# Drone_Mercury.net
KiCad netlist of a schematic drawn in Altium Designer
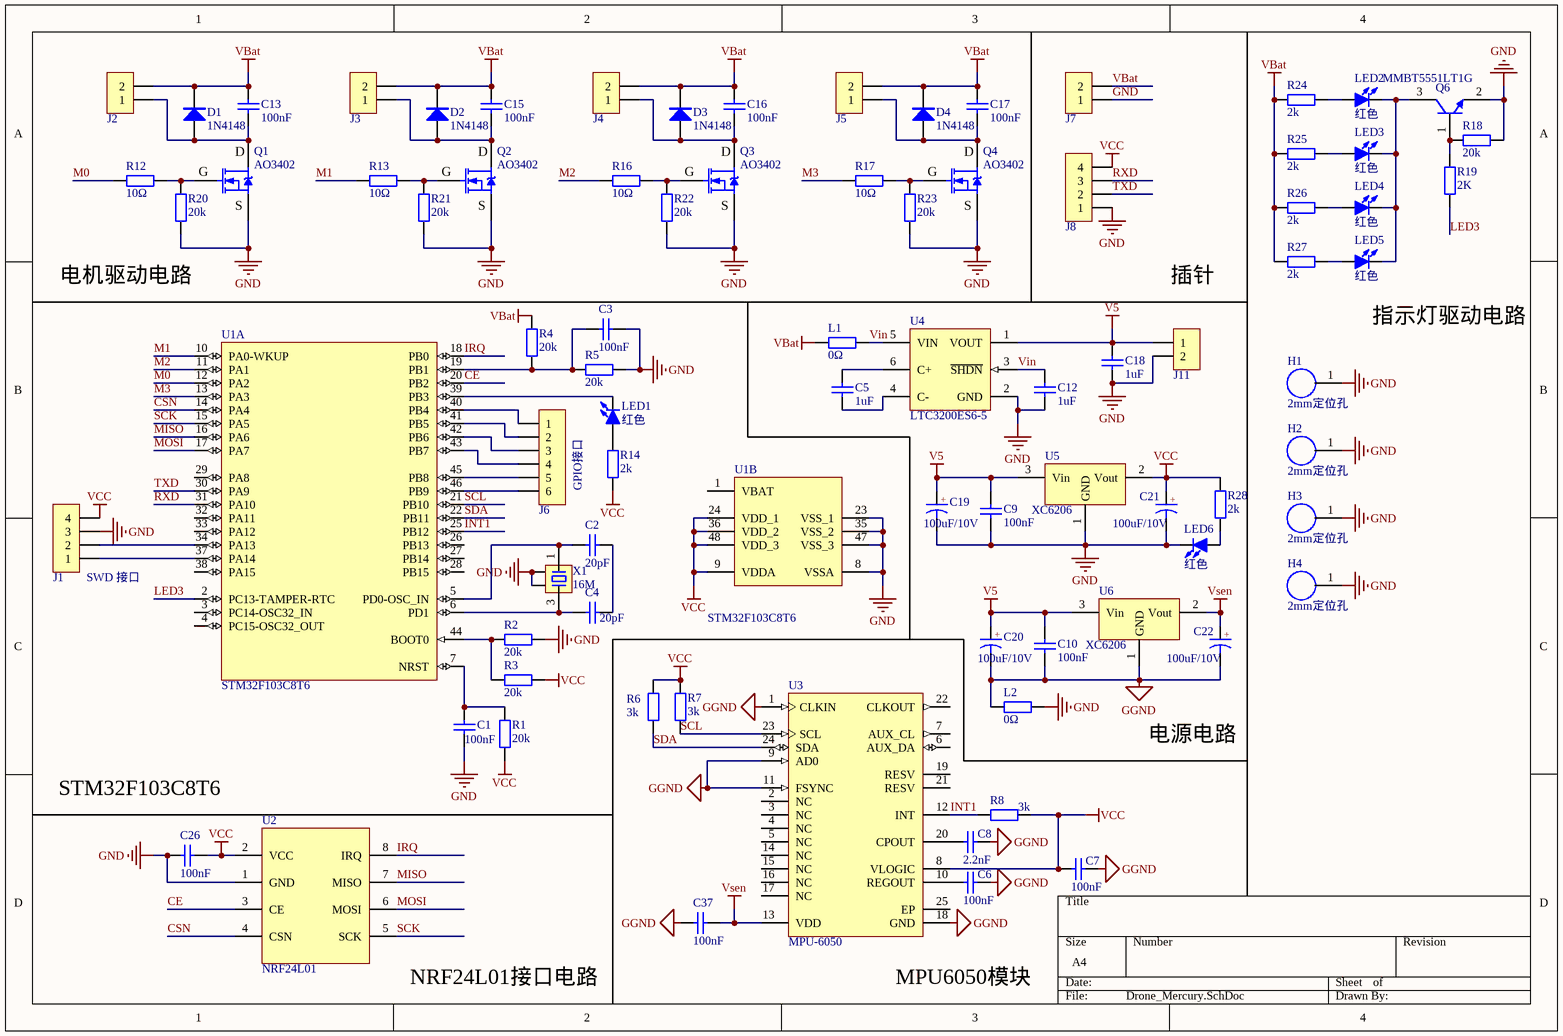
[diagram p0: Drone_Mercury.SchDoc]

(export (version "E")
  (design (tool "Eeschema 10.0.6"))
  (components
    (comp (ref "C1")
      (value "100nF")
      (footprint "C0603_M")
      (description "贴片电容")
      (libsource (lib "0.1 - 电阻-电容-电感-晶振-晶体-磁珠-电位器") (part "C"))
    )
    (comp (ref "C2")
      (value "20pF")
      (footprint "C0603_M")
      (description "贴片电容")
      (libsource (lib "0.1 - 电阻-电容-电感-晶振-晶体-磁珠-电位器") (part "C"))
    )
    (comp (ref "C3")
      (value "100nF")
      (footprint "C0603_M")
      (description "贴片电容")
      (libsource (lib "0.1 - 电阻-电容-电感-晶振-晶体-磁珠-电位器") (part "C"))
    )
    (comp (ref "C4")
      (value "20pF")
      (footprint "C0603_M")
      (description "贴片电容")
      (libsource (lib "0.1 - 电阻-电容-电感-晶振-晶体-磁珠-电位器") (part "C"))
    )
    (comp (ref "C5")
      (value "1uF")
      (footprint "C0603_M")
      (description "贴片电容")
      (libsource (lib "0.1 - 电阻-电容-电感-晶振-晶体-磁珠-电位器") (part "C"))
    )
    (comp (ref "C6")
      (value "100nF")
      (footprint "C0603_M")
      (description "贴片电容")
      (libsource (lib "0.1 - 电阻-电容-电感-晶振-晶体-磁珠-电位器") (part "C"))
    )
    (comp (ref "C7")
      (value "100nF")
      (footprint "C0603_M")
      (description "贴片电容")
      (libsource (lib "0.1 - 电阻-电容-电感-晶振-晶体-磁珠-电位器") (part "C"))
    )
    (comp (ref "C8")
      (value "2.2nF")
      (footprint "C0603_M")
      (description "贴片电容")
      (libsource (lib "0.1 - 电阻-电容-电感-晶振-晶体-磁珠-电位器") (part "C"))
    )
    (comp (ref "C9")
      (value "100nF")
      (footprint "C0603_M")
      (description "贴片电容")
      (libsource (lib "0.1 - 电阻-电容-电感-晶振-晶体-磁珠-电位器") (part "C"))
    )
    (comp (ref "C10")
      (value "100nF")
      (footprint "C0603_M")
      (description "贴片电容")
      (libsource (lib "0.1 - 电阻-电容-电感-晶振-晶体-磁珠-电位器") (part "C"))
    )
    (comp (ref "C12")
      (value "1uF")
      (footprint "C0603_M")
      (description "贴片电容")
      (libsource (lib "0.1 - 电阻-电容-电感-晶振-晶体-磁珠-电位器") (part "C"))
    )
    (comp (ref "C13")
      (value "100nF")
      (footprint "C0603_M")
      (description "贴片电容")
      (libsource (lib "0.1 - 电阻-电容-电感-晶振-晶体-磁珠-电位器") (part "C"))
    )
    (comp (ref "C15")
      (value "100nF")
      (footprint "C0603_M")
      (description "贴片电容")
      (libsource (lib "0.1 - 电阻-电容-电感-晶振-晶体-磁珠-电位器") (part "C"))
    )
    (comp (ref "C16")
      (value "100nF")
      (footprint "C0603_M")
      (description "贴片电容")
      (libsource (lib "0.1 - 电阻-电容-电感-晶振-晶体-磁珠-电位器") (part "C"))
    )
    (comp (ref "C17")
      (value "100nF")
      (footprint "C0603_M")
      (description "贴片电容")
      (libsource (lib "0.1 - 电阻-电容-电感-晶振-晶体-磁珠-电位器") (part "C"))
    )
    (comp (ref "C18")
      (value "1uF")
      (footprint "C0603_M")
      (description "贴片电容")
      (libsource (lib "0.1 - 电阻-电容-电感-晶振-晶体-磁珠-电位器") (part "C"))
    )
    (comp (ref "C19")
      (value "100uF/10V")
      (footprint "C_3528")
      (description "贴片钽电容")
      (libsource (lib "0.1 - 电阻-电容-电感-晶振-晶体-磁珠-电位器") (part "CT"))
    )
    (comp (ref "C20")
      (value "100uF/10V")
      (footprint "C_3528")
      (description "贴片钽电容")
      (libsource (lib "0.1 - 电阻-电容-电感-晶振-晶体-磁珠-电位器") (part "CT"))
    )
    (comp (ref "C21")
      (value "100uF/10V")
      (footprint "C_3528")
      (description "贴片钽电容")
      (libsource (lib "0.1 - 电阻-电容-电感-晶振-晶体-磁珠-电位器") (part "CT"))
    )
    (comp (ref "C22")
      (value "100uF/10V")
      (footprint "C_3528")
      (description "贴片钽电容")
      (libsource (lib "0.1 - 电阻-电容-电感-晶振-晶体-磁珠-电位器") (part "CT"))
    )
    (comp (ref "C26")
      (value "100nF")
      (footprint "C0603_M")
      (description "贴片电容")
      (libsource (lib "0.1 - 电阻-电容-电感-晶振-晶体-磁珠-电位器") (part "C"))
    )
    (comp (ref "C37")
      (value "100nF")
      (footprint "C0603_M")
      (description "贴片电容")
      (libsource (lib "0.1 - 电阻-电容-电感-晶振-晶体-磁珠-电位器") (part "C"))
    )
    (comp (ref "D1")
      (value "1N4148")
      (footprint "SOD-323")
      (description "开关二极管")
      (libsource (lib "0.2 - 二极管-TVS-ESD-整流桥") (part "1N4148"))
    )
    (comp (ref "D2")
      (value "1N4148")
      (footprint "SOD-323")
      (description "开关二极管")
      (libsource (lib "0.2 - 二极管-TVS-ESD-整流桥") (part "1N4148"))
    )
    (comp (ref "D3")
      (value "1N4148")
      (footprint "SOD-323")
      (description "开关二极管")
      (libsource (lib "0.2 - 二极管-TVS-ESD-整流桥") (part "1N4148"))
    )
    (comp (ref "D4")
      (value "1N4148")
      (footprint "SOD-323")
      (description "开关二极管")
      (libsource (lib "0.2 - 二极管-TVS-ESD-整流桥") (part "1N4148"))
    )
    (comp (ref "H1") (value "2mm定位孔") (footprint "Pos-Hole") (libsource (lib "mercury") (part "Hole")))
    (comp (ref "H2") (value "2mm定位孔") (footprint "Pos-Hole") (libsource (lib "mercury") (part "Hole")))
    (comp (ref "H3") (value "2mm定位孔") (footprint "Pos-Hole") (libsource (lib "mercury") (part "Hole")))
    (comp (ref "H4") (value "2mm定位孔") (footprint "Pos-Hole") (libsource (lib "mercury") (part "Hole")))
    (comp (ref "J1")
      (value "SWD")
      (footprint "HDR2.54-LI-4P")
      (description "4P接插件")
      (libsource (lib "5.5 - 2.54mm(100mil)连接器(XH2.54)") (part "Header 4"))
    )
    (comp (ref "J2")
      (value "电机SH1.0插母")
      (footprint "SH1.0-2p")
      (description "2P接插件")
      (libsource (lib "5.5 - 2.54mm(100mil)连接器(XH2.54)") (part "Header 2"))
    )
    (comp (ref "J3")
      (value "电机SH1.0插母")
      (footprint "SH1.0-2p")
      (description "2P接插件")
      (libsource (lib "5.5 - 2.54mm(100mil)连接器(XH2.54)") (part "Header 2"))
    )
    (comp (ref "J4")
      (value "电机SH1.0插母")
      (footprint "SH1.0-2p")
      (description "2P接插件")
      (libsource (lib "5.5 - 2.54mm(100mil)连接器(XH2.54)") (part "Header 2"))
    )
    (comp (ref "J5")
      (value "电机SH1.0插母")
      (footprint "SH1.0-2p")
      (description "2P接插件")
      (libsource (lib "5.5 - 2.54mm(100mil)连接器(XH2.54)") (part "Header 2"))
    )
    (comp (ref "J6")
      (value "HDR-1X6")
      (footprint "HDR2.54-LI-6P")
      (description "GPIO口")
      (libsource (lib "5.5 - 2.54mm(100mil)连接器(XH2.54)") (part "Header 6"))
    )
    (comp (ref "J7")
      (value "电源线")
      (footprint "Drone_mercury:PWR_Bonding_Pad")
      (description "2P接插件")
      (libsource (lib "5.5 - 2.54mm(100mil)连接器(XH2.54)") (part "Header 2"))
    )
    (comp (ref "J8")
      (value "HDR-1X4")
      (footprint "HDR2.54-LI-4P")
      (description "UART通信口")
      (libsource (lib "5.5 - 2.54mm(100mil)连接器(XH2.54)") (part "Header 4"))
    )
    (comp (ref "J11")
      (value "HDR-1X2")
      (footprint "HDR2.54-LI-2P")
      (description "2P接插件")
      (libsource (lib "") (part "Header 2_1"))
    )
    (comp (ref "L1")
      (value "0Ω")
      (footprint "R0805_L")
      (description "贴片电阻")
      (libsource (lib "0.1 - 电阻-电容-电感-晶振-晶体-磁珠-电位器") (part "R"))
    )
    (comp (ref "L2")
      (value "0Ω")
      (footprint "R0805_L")
      (description "贴片电阻")
      (libsource (lib "0.1 - 电阻-电容-电感-晶振-晶体-磁珠-电位器") (part "R"))
    )
    (comp (ref "LED1")
      (value "红色")
      (footprint "LED0603_R")
      (description "贴片LED")
      (libsource (lib "0.3 - LED发光二极管-IR二极管_接收管-光耦") (part "LED-SMD"))
    )
    (comp (ref "LED2")
      (value "红色")
      (footprint "LED0603_R")
      (description "贴片LED")
      (libsource (lib "0.3 - LED发光二极管-IR二极管_接收管-光耦") (part "LED-SMD"))
    )
    (comp (ref "LED3")
      (value "红色")
      (footprint "LED0603_R")
      (description "贴片LED")
      (libsource (lib "0.3 - LED发光二极管-IR二极管_接收管-光耦") (part "LED-SMD"))
    )
    (comp (ref "LED4")
      (value "红色")
      (footprint "LED0603_R")
      (description "贴片LED")
      (libsource (lib "0.3 - LED发光二极管-IR二极管_接收管-光耦") (part "LED-SMD"))
    )
    (comp (ref "LED5")
      (value "红色")
      (footprint "LED0603_R")
      (description "贴片LED")
      (libsource (lib "0.3 - LED发光二极管-IR二极管_接收管-光耦") (part "LED-SMD"))
    )
    (comp (ref "LED6")
      (value "红色")
      (footprint "LED0603_R")
      (description "贴片LED")
      (libsource (lib "0.3 - LED发光二极管-IR二极管_接收管-光耦") (part "LED-SMD"))
    )
    (comp (ref "Q1")
      (value "AO3402")
      (footprint "SOT23-3N")
      (description "N沟道 30V/4.2A")
      (libsource (lib "0.4 - 三极管-场效应管-可控硅") (part "AO3400"))
    )
    (comp (ref "Q2")
      (value "AO3402")
      (footprint "SOT23-3N")
      (description "N沟道 30V/4.2A")
      (libsource (lib "0.4 - 三极管-场效应管-可控硅") (part "AO3400"))
    )
    (comp (ref "Q3")
      (value "AO3402")
      (footprint "SOT23-3N")
      (description "N沟道 30V/4.2A")
      (libsource (lib "0.4 - 三极管-场效应管-可控硅") (part "AO3400"))
    )
    (comp (ref "Q4")
      (value "AO3402")
      (footprint "SOT23-3N")
      (description "N沟道 30V/4.2A")
      (libsource (lib "0.4 - 三极管-场效应管-可控硅") (part "AO3400"))
    )
    (comp (ref "Q6")
      (value "MMBT5551LT1G")
      (footprint "ONSC-SOT-23-3-318-08_V")
      (description "High Voltage Transistor, NPN Silicon, 3-Pin SOT-23, Pb-Free, Tape and Reel")
      (fields (field (name "MANUFACTURER") "On Semiconductor"))
      (libsource (lib "Altium Content Vault") (part "ONSC-NPN-B1E2C3-3"))
    )
    (comp (ref "R1")
      (value "20k")
      (footprint "R0603_M")
      (description "贴片电阻")
      (libsource (lib "0.1 - 电阻-电容-电感-晶振-晶体-磁珠-电位器") (part "R"))
    )
    (comp (ref "R2")
      (value "20k")
      (footprint "R0603_M")
      (description "贴片电阻")
      (libsource (lib "0.1 - 电阻-电容-电感-晶振-晶体-磁珠-电位器") (part "R"))
    )
    (comp (ref "R3")
      (value "20k")
      (footprint "R0603_M")
      (description "贴片电阻")
      (libsource (lib "0.1 - 电阻-电容-电感-晶振-晶体-磁珠-电位器") (part "R"))
    )
    (comp (ref "R4")
      (value "20k")
      (footprint "R0603_M")
      (description "贴片电阻")
      (libsource (lib "0.1 - 电阻-电容-电感-晶振-晶体-磁珠-电位器") (part "R"))
    )
    (comp (ref "R5")
      (value "20k")
      (footprint "R0603_M")
      (description "贴片电阻")
      (libsource (lib "0.1 - 电阻-电容-电感-晶振-晶体-磁珠-电位器") (part "R"))
    )
    (comp (ref "R6")
      (value "3k")
      (footprint "R0603_M")
      (description "贴片电阻")
      (libsource (lib "0.1 - 电阻-电容-电感-晶振-晶体-磁珠-电位器") (part "R"))
    )
    (comp (ref "R7")
      (value "3k")
      (footprint "R0603_M")
      (description "贴片电阻")
      (libsource (lib "0.1 - 电阻-电容-电感-晶振-晶体-磁珠-电位器") (part "R"))
    )
    (comp (ref "R8")
      (value "3k")
      (footprint "R0603_M")
      (description "贴片电阻")
      (libsource (lib "0.1 - 电阻-电容-电感-晶振-晶体-磁珠-电位器") (part "R"))
    )
    (comp (ref "R12")
      (value "10Ω")
      (footprint "R0603_M")
      (description "贴片电阻")
      (libsource (lib "0.1 - 电阻-电容-电感-晶振-晶体-磁珠-电位器") (part "R"))
    )
    (comp (ref "R13")
      (value "10Ω")
      (footprint "R0603_M")
      (description "贴片电阻")
      (libsource (lib "0.1 - 电阻-电容-电感-晶振-晶体-磁珠-电位器") (part "R"))
    )
    (comp (ref "R14")
      (value "2k")
      (footprint "R0603_M")
      (description "贴片电阻")
      (libsource (lib "0.1 - 电阻-电容-电感-晶振-晶体-磁珠-电位器") (part "R"))
    )
    (comp (ref "R16")
      (value "10Ω")
      (footprint "R0603_M")
      (description "贴片电阻")
      (libsource (lib "0.1 - 电阻-电容-电感-晶振-晶体-磁珠-电位器") (part "R"))
    )
    (comp (ref "R17")
      (value "10Ω")
      (footprint "R0603_M")
      (description "贴片电阻")
      (libsource (lib "0.1 - 电阻-电容-电感-晶振-晶体-磁珠-电位器") (part "R"))
    )
    (comp (ref "R18")
      (value "20k")
      (footprint "R0603_M")
      (description "贴片电阻")
      (libsource (lib "0.1 - 电阻-电容-电感-晶振-晶体-磁珠-电位器") (part "R"))
    )
    (comp (ref "R19")
      (value "2K")
      (footprint "R0603_M")
      (description "贴片电阻")
      (libsource (lib "0.1 - 电阻-电容-电感-晶振-晶体-磁珠-电位器") (part "R"))
    )
    (comp (ref "R20")
      (value "20k")
      (footprint "R0603_M")
      (description "贴片电阻")
      (libsource (lib "0.1 - 电阻-电容-电感-晶振-晶体-磁珠-电位器") (part "R"))
    )
    (comp (ref "R21")
      (value "20k")
      (footprint "R0603_M")
      (description "贴片电阻")
      (libsource (lib "0.1 - 电阻-电容-电感-晶振-晶体-磁珠-电位器") (part "R"))
    )
    (comp (ref "R22")
      (value "20k")
      (footprint "R0603_M")
      (description "贴片电阻")
      (libsource (lib "0.1 - 电阻-电容-电感-晶振-晶体-磁珠-电位器") (part "R"))
    )
    (comp (ref "R23")
      (value "20k")
      (footprint "R0603_M")
      (description "贴片电阻")
      (libsource (lib "0.1 - 电阻-电容-电感-晶振-晶体-磁珠-电位器") (part "R"))
    )
    (comp (ref "R24")
      (value "2k")
      (footprint "R0603_M")
      (description "贴片电阻")
      (libsource (lib "0.1 - 电阻-电容-电感-晶振-晶体-磁珠-电位器") (part "R"))
    )
    (comp (ref "R25")
      (value "2k")
      (footprint "R0603_M")
      (description "贴片电阻")
      (libsource (lib "0.1 - 电阻-电容-电感-晶振-晶体-磁珠-电位器") (part "R"))
    )
    (comp (ref "R26")
      (value "2k")
      (footprint "R0603_M")
      (description "贴片电阻")
      (libsource (lib "0.1 - 电阻-电容-电感-晶振-晶体-磁珠-电位器") (part "R"))
    )
    (comp (ref "R27")
      (value "2k")
      (footprint "R0603_M")
      (description "贴片电阻")
      (libsource (lib "0.1 - 电阻-电容-电感-晶振-晶体-磁珠-电位器") (part "R"))
    )
    (comp (ref "R28")
      (value "2k")
      (footprint "R0603_M")
      (description "贴片电阻")
      (libsource (lib "0.1 - 电阻-电容-电感-晶振-晶体-磁珠-电位器") (part "R"))
    )
    (comp (ref "U1")
      (value "STM32F103C8T6")
      (footprint "LQFP48_N")
      (libsource (lib "2.4 - STM32 F1系列单片机") (part "STM32F103C8T6"))
    )
    (comp (ref "U2")
      (value "NRF24L01")
      (footprint "HDR2.54-M-LS-2x4P")
      (libsource (lib "mercury") (part "NRF24L01"))
    )
    (comp (ref "U3")
      (value "MPU-6050")
      (footprint "IS-QFN-24_V")
      (fields (field (name "MANUFACTURER") "InvenSense"))
      (libsource (lib "Altium Content Vault") (part "IS-MPU-6050-QFN-24"))
    )
    (comp (ref "U4")
      (value "LTC3200ES6-5")
      (footprint "LT-S6-6-TSOT-23_M")
      (fields
        (field (name "MANUFACTURER") "Linear Technology")
        (field (name "PARTNUMBER") "LTC3200ES6-5#TRMPBF")
      )
      (libsource (lib "Altium Content Vault") (part "LT-LTC1754_3200-S6-6"))
    )
    (comp (ref "U5") (value "XC6206") (footprint "sot23") (libsource (lib "mercury") (part "XC6206")))
    (comp (ref "U6") (value "XC6206") (footprint "sot23") (libsource (lib "mercury") (part "XC6206")))
    (comp (ref "X1")
      (value "16M")
      (footprint "XTAL-3225-4P")
      (description "4脚无源晶振(谐振器）")
      (libsource (lib "0.1 - 电阻-电容-电感-晶振-晶体-磁珠-电位器") (part "XTAL-4P"))
    )
  )
  (nets
    (net (code "1") (name "/CE") (class "Default")
      (node (ref "U1") (pin "20") (pinfunction "PB2_20") (pintype "bidirectional"))
      (node (ref "U2") (pin "3") (pinfunction "CE_3") (pintype "passive"))
    )
    (net (code "2") (name "/CSN") (class "Default")
      (node (ref "U1") (pin "14") (pinfunction "PA4_14") (pintype "bidirectional"))
      (node (ref "U2") (pin "4") (pinfunction "CSN_4") (pintype "passive"))
    )
    (net (code "3") (name "/INT1") (class "Default")
      (node (ref "R8") (pin "2") (pinfunction "2_2") (pintype "passive"))
      (node (ref "U1") (pin "25") (pinfunction "PB12_25") (pintype "bidirectional"))
      (node (ref "U3") (pin "12") (pinfunction "INT_12") (pintype "open_collector"))
    )
    (net (code "4") (name "/IRQ") (class "Default")
      (node (ref "U1") (pin "18") (pinfunction "PB0_18") (pintype "bidirectional"))
      (node (ref "U2") (pin "8") (pinfunction "IRQ_8") (pintype "passive"))
    )
    (net (code "5") (name "/LED3") (class "Default")
      (node (ref "R19") (pin "2") (pinfunction "2_2") (pintype "passive"))
      (node (ref "U1") (pin "2") (pinfunction "PC13-TAMPER-RTC_2") (pintype "bidirectional"))
    )
    (net (code "6") (name "/M0") (class "Default")
      (node (ref "R12") (pin "1") (pinfunction "1_1") (pintype "passive"))
      (node (ref "U1") (pin "12") (pinfunction "PA2_12") (pintype "bidirectional"))
    )
    (net (code "7") (name "/M1") (class "Default")
      (node (ref "R13") (pin "1") (pinfunction "1_1") (pintype "passive"))
      (node (ref "U1") (pin "10") (pinfunction "PA0-WKUP_10") (pintype "bidirectional"))
    )
    (net (code "8") (name "/M2") (class "Default")
      (node (ref "R16") (pin "1") (pinfunction "1_1") (pintype "passive"))
      (node (ref "U1") (pin "11") (pinfunction "PA1_11") (pintype "bidirectional"))
    )
    (net (code "9") (name "/M3") (class "Default")
      (node (ref "R17") (pin "1") (pinfunction "1_1") (pintype "passive"))
      (node (ref "U1") (pin "13") (pinfunction "PA3_13") (pintype "bidirectional"))
    )
    (net (code "10") (name "/MISO") (class "Default")
      (node (ref "U1") (pin "16") (pinfunction "PA6_16") (pintype "bidirectional"))
      (node (ref "U2") (pin "7") (pinfunction "MISO_7") (pintype "passive"))
    )
    (net (code "11") (name "/MOSI") (class "Default")
      (node (ref "U1") (pin "17") (pinfunction "PA7_17") (pintype "bidirectional"))
      (node (ref "U2") (pin "6") (pinfunction "MOSI_6") (pintype "passive"))
    )
    (net (code "12") (name "/RXD") (class "Default")
      (node (ref "J8") (pin "3") (pinfunction "3_3") (pintype "passive"))
      (node (ref "U1") (pin "31") (pinfunction "PA10_31") (pintype "bidirectional"))
    )
    (net (code "13") (name "/SCK") (class "Default")
      (node (ref "U1") (pin "15") (pinfunction "PA5_15") (pintype "bidirectional"))
      (node (ref "U2") (pin "5") (pinfunction "SCK_5") (pintype "passive"))
    )
    (net (code "14") (name "/SCL") (class "Default")
      (node (ref "R7") (pin "1") (pinfunction "1_1") (pintype "passive"))
      (node (ref "U1") (pin "21") (pinfunction "PB10_21") (pintype "bidirectional"))
      (node (ref "U3") (pin "23") (pinfunction "SCL_23") (pintype "input"))
    )
    (net (code "15") (name "/SDA") (class "Default")
      (node (ref "R6") (pin "1") (pinfunction "1_1") (pintype "passive"))
      (node (ref "U1") (pin "22") (pinfunction "PB11_22") (pintype "bidirectional"))
      (node (ref "U3") (pin "24") (pinfunction "SDA_24") (pintype "bidirectional"))
    )
    (net (code "16") (name "/TXD") (class "Default")
      (node (ref "J8") (pin "2") (pinfunction "2_2") (pintype "passive"))
      (node (ref "U1") (pin "30") (pinfunction "PA9_30") (pintype "bidirectional"))
    )
    (net (code "17") (name "/Vin") (class "Default")
      (node (ref "C12") (pin "2") (pinfunction "2_2") (pintype "passive"))
      (node (ref "L1") (pin "1") (pinfunction "1_1") (pintype "passive"))
      (node (ref "U4") (pin "3") (pinfunction "~{SHDN}_3") (pintype "input"))
      (node (ref "U4") (pin "5") (pinfunction "VIN_5") (pintype "power_in"))
    )
    (net (code "18") (name "GGND") (class "Default")
      (node (ref "C10") (pin "1") (pinfunction "1_1") (pintype "passive"))
      (node (ref "C20") (pin "2") (pinfunction "K_2") (pintype "passive"))
      (node (ref "C22") (pin "2") (pinfunction "K_2") (pintype "passive"))
      (node (ref "C37") (pin "2") (pinfunction "2_2") (pintype "passive"))
      (node (ref "C6") (pin "1") (pinfunction "1_1") (pintype "passive"))
      (node (ref "C7") (pin "1") (pinfunction "1_1") (pintype "passive"))
      (node (ref "C8") (pin "1") (pinfunction "1_1") (pintype "passive"))
      (node (ref "L2") (pin "2") (pinfunction "2_2") (pintype "passive"))
      (node (ref "U3") (pin "1") (pinfunction "CLKIN_1") (pintype "input"))
      (node (ref "U3") (pin "11") (pinfunction "FSYNC_11") (pintype "input"))
      (node (ref "U3") (pin "18") (pinfunction "GND_18") (pintype "power_in"))
      (node (ref "U3") (pin "9") (pinfunction "AD0_9") (pintype "input"))
      (node (ref "U6") (pin "1") (pinfunction "GND_1") (pintype "passive"))
    )
    (net (code "19") (name "GND") (class "Default")
      (node (ref "C1") (pin "1") (pinfunction "1_1") (pintype "passive"))
      (node (ref "C12") (pin "1") (pinfunction "1_1") (pintype "passive"))
      (node (ref "C18") (pin "1") (pinfunction "1_1") (pintype "passive"))
      (node (ref "C19") (pin "2") (pinfunction "K_2") (pintype "passive"))
      (node (ref "C21") (pin "2") (pinfunction "K_2") (pintype "passive"))
      (node (ref "C26") (pin "2") (pinfunction "2_2") (pintype "passive"))
      (node (ref "C3") (pin "1") (pinfunction "1_1") (pintype "passive"))
      (node (ref "C9") (pin "1") (pinfunction "1_1") (pintype "passive"))
      (node (ref "H1") (pin "1") (pintype "passive"))
      (node (ref "H2") (pin "1") (pintype "passive"))
      (node (ref "H3") (pin "1") (pintype "passive"))
      (node (ref "H4") (pin "1") (pintype "passive"))
      (node (ref "J1") (pin "3") (pinfunction "3_3") (pintype "passive"))
      (node (ref "J11") (pin "2") (pinfunction "2_2") (pintype "passive"))
      (node (ref "J7") (pin "1") (pinfunction "1_1") (pintype "passive"))
      (node (ref "J8") (pin "1") (pinfunction "1_1") (pintype "passive"))
      (node (ref "L2") (pin "1") (pinfunction "1_1") (pintype "passive"))
      (node (ref "LED6") (pin "2") (pinfunction "K_2") (pintype "passive"))
      (node (ref "Q1") (pin "2") (pinfunction "S_2") (pintype "passive"))
      (node (ref "Q2") (pin "2") (pinfunction "S_2") (pintype "passive"))
      (node (ref "Q3") (pin "2") (pinfunction "S_2") (pintype "passive"))
      (node (ref "Q4") (pin "2") (pinfunction "S_2") (pintype "passive"))
      (node (ref "Q6") (pin "2") (pinfunction "E_2") (pintype "passive"))
      (node (ref "R18") (pin "2") (pinfunction "2_2") (pintype "passive"))
      (node (ref "R2") (pin "1") (pinfunction "1_1") (pintype "passive"))
      (node (ref "R20") (pin "1") (pinfunction "1_1") (pintype "passive"))
      (node (ref "R21") (pin "1") (pinfunction "1_1") (pintype "passive"))
      (node (ref "R22") (pin "1") (pinfunction "1_1") (pintype "passive"))
      (node (ref "R23") (pin "1") (pinfunction "1_1") (pintype "passive"))
      (node (ref "R5") (pin "2") (pinfunction "2_2") (pintype "passive"))
      (node (ref "U1") (pin "23") (pinfunction "VSS_1_23") (pintype "power_in"))
      (node (ref "U1") (pin "35") (pinfunction "VSS_2_35") (pintype "power_in"))
      (node (ref "U1") (pin "47") (pinfunction "VSS_3_47") (pintype "power_in"))
      (node (ref "U1") (pin "8") (pinfunction "VSSA_8") (pintype "power_in"))
      (node (ref "U2") (pin "1") (pinfunction "GND_1") (pintype "passive"))
      (node (ref "U4") (pin "2") (pinfunction "GND_2") (pintype "power_in"))
      (node (ref "U5") (pin "1") (pinfunction "GND_1") (pintype "passive"))
      (node (ref "X1") (pin "2") (pinfunction "2_2") (pintype "passive"))
      (node (ref "X1") (pin "4") (pinfunction "4_4") (pintype "passive"))
    )
    (net (code "20") (name "Net-(C2-Pad2)") (class "Default")
      (node (ref "C2") (pin "2") (pinfunction "2_2") (pintype "passive"))
      (node (ref "C4") (pin "2") (pinfunction "2_2") (pintype "passive"))
    )
    (net (code "21") (name "Net-(D1-A)") (class "Default")
      (node (ref "C13") (pin "1") (pinfunction "1_1") (pintype "passive"))
      (node (ref "D1") (pin "1") (pinfunction "A_1") (pintype "passive"))
      (node (ref "J2") (pin "1") (pinfunction "1_1") (pintype "passive"))
      (node (ref "Q1") (pin "3") (pinfunction "D_3") (pintype "passive"))
    )
    (net (code "22") (name "Net-(D2-A)") (class "Default")
      (node (ref "C15") (pin "1") (pinfunction "1_1") (pintype "passive"))
      (node (ref "D2") (pin "1") (pinfunction "A_1") (pintype "passive"))
      (node (ref "J3") (pin "1") (pinfunction "1_1") (pintype "passive"))
      (node (ref "Q2") (pin "3") (pinfunction "D_3") (pintype "passive"))
    )
    (net (code "23") (name "Net-(D3-A)") (class "Default")
      (node (ref "C16") (pin "1") (pinfunction "1_1") (pintype "passive"))
      (node (ref "D3") (pin "1") (pinfunction "A_1") (pintype "passive"))
      (node (ref "J4") (pin "1") (pinfunction "1_1") (pintype "passive"))
      (node (ref "Q3") (pin "3") (pinfunction "D_3") (pintype "passive"))
    )
    (net (code "24") (name "Net-(D4-A)") (class "Default")
      (node (ref "C17") (pin "1") (pinfunction "1_1") (pintype "passive"))
      (node (ref "D4") (pin "1") (pinfunction "A_1") (pintype "passive"))
      (node (ref "J5") (pin "1") (pinfunction "1_1") (pintype "passive"))
      (node (ref "Q4") (pin "3") (pinfunction "D_3") (pintype "passive"))
    )
    (net (code "25") (name "Net-(LED1-A)") (class "Default")
      (node (ref "LED1") (pin "1") (pinfunction "A_1") (pintype "passive"))
      (node (ref "R14") (pin "2") (pinfunction "2_2") (pintype "passive"))
    )
    (net (code "26") (name "Net-(LED1-K)") (class "Default")
      (node (ref "LED1") (pin "2") (pinfunction "K_2") (pintype "passive"))
      (node (ref "U1") (pin "39") (pinfunction "PB3_39") (pintype "bidirectional"))
    )
    (net (code "27") (name "Net-(LED2-A)") (class "Default")
      (node (ref "LED2") (pin "1") (pinfunction "A_1") (pintype "passive"))
      (node (ref "R24") (pin "1") (pinfunction "1_1") (pintype "passive"))
    )
    (net (code "28") (name "Net-(LED2-K)") (class "Default")
      (node (ref "LED2") (pin "2") (pinfunction "K_2") (pintype "passive"))
      (node (ref "LED3") (pin "2") (pinfunction "K_2") (pintype "passive"))
      (node (ref "LED4") (pin "2") (pinfunction "K_2") (pintype "passive"))
      (node (ref "LED5") (pin "2") (pinfunction "K_2") (pintype "passive"))
      (node (ref "Q6") (pin "3") (pinfunction "C_3") (pintype "passive"))
    )
    (net (code "29") (name "Net-(LED3-A)") (class "Default")
      (node (ref "LED3") (pin "1") (pinfunction "A_1") (pintype "passive"))
      (node (ref "R25") (pin "1") (pinfunction "1_1") (pintype "passive"))
    )
    (net (code "30") (name "Net-(LED4-A)") (class "Default")
      (node (ref "LED4") (pin "1") (pinfunction "A_1") (pintype "passive"))
      (node (ref "R26") (pin "1") (pinfunction "1_1") (pintype "passive"))
    )
    (net (code "31") (name "Net-(LED5-A)") (class "Default")
      (node (ref "LED5") (pin "1") (pinfunction "A_1") (pintype "passive"))
      (node (ref "R27") (pin "1") (pinfunction "1_1") (pintype "passive"))
    )
    (net (code "32") (name "Net-(LED6-A)") (class "Default")
      (node (ref "LED6") (pin "1") (pinfunction "A_1") (pintype "passive"))
      (node (ref "R28") (pin "1") (pinfunction "1_1") (pintype "passive"))
    )
    (net (code "33") (name "Net-(Q1-G)") (class "Default")
      (node (ref "Q1") (pin "1") (pinfunction "G_1") (pintype "passive"))
      (node (ref "R12") (pin "2") (pinfunction "2_2") (pintype "passive"))
      (node (ref "R20") (pin "2") (pinfunction "2_2") (pintype "passive"))
    )
    (net (code "34") (name "Net-(Q2-G)") (class "Default")
      (node (ref "Q2") (pin "1") (pinfunction "G_1") (pintype "passive"))
      (node (ref "R13") (pin "2") (pinfunction "2_2") (pintype "passive"))
      (node (ref "R21") (pin "2") (pinfunction "2_2") (pintype "passive"))
    )
    (net (code "35") (name "Net-(Q3-G)") (class "Default")
      (node (ref "Q3") (pin "1") (pinfunction "G_1") (pintype "passive"))
      (node (ref "R16") (pin "2") (pinfunction "2_2") (pintype "passive"))
      (node (ref "R22") (pin "2") (pinfunction "2_2") (pintype "passive"))
    )
    (net (code "36") (name "Net-(Q4-G)") (class "Default")
      (node (ref "Q4") (pin "1") (pinfunction "G_1") (pintype "passive"))
      (node (ref "R17") (pin "2") (pinfunction "2_2") (pintype "passive"))
      (node (ref "R23") (pin "2") (pinfunction "2_2") (pintype "passive"))
    )
    (net (code "37") (name "Net-(Q6-B)") (class "Default")
      (node (ref "Q6") (pin "1") (pinfunction "B_1") (pintype "passive"))
      (node (ref "R18") (pin "1") (pinfunction "1_1") (pintype "passive"))
      (node (ref "R19") (pin "1") (pinfunction "1_1") (pintype "passive"))
    )
    (net (code "38") (name "Net-(U1A-BOOT0)") (class "Default")
      (node (ref "R2") (pin "2") (pinfunction "2_2") (pintype "passive"))
      (node (ref "R3") (pin "2") (pinfunction "2_2") (pintype "passive"))
      (node (ref "U1") (pin "44") (pinfunction "BOOT0_44") (pintype "input"))
    )
    (net (code "39") (name "Net-(U1A-NRST)") (class "Default")
      (node (ref "C1") (pin "2") (pinfunction "2_2") (pintype "passive"))
      (node (ref "R1") (pin "2") (pinfunction "2_2") (pintype "passive"))
      (node (ref "U1") (pin "7") (pinfunction "NRST_7") (pintype "bidirectional"))
    )
    (net (code "40") (name "Net-(U1A-PA13)") (class "Default")
      (node (ref "J1") (pin "2") (pinfunction "2_2") (pintype "passive"))
      (node (ref "U1") (pin "34") (pinfunction "PA13_34") (pintype "bidirectional"))
    )
    (net (code "41") (name "Net-(U1A-PA14)") (class "Default")
      (node (ref "J1") (pin "1") (pinfunction "1_1") (pintype "passive"))
      (node (ref "U1") (pin "37") (pinfunction "PA14_37") (pintype "bidirectional"))
    )
    (net (code "42") (name "Net-(U1A-PB1)") (class "Default")
      (node (ref "C3") (pin "2") (pinfunction "2_2") (pintype "passive"))
      (node (ref "R4") (pin "2") (pinfunction "2_2") (pintype "passive"))
      (node (ref "R5") (pin "1") (pinfunction "1_1") (pintype "passive"))
      (node (ref "U1") (pin "19") (pinfunction "PB1_19") (pintype "bidirectional"))
    )
    (net (code "43") (name "Net-(U1A-PB4)") (class "Default")
      (node (ref "J6") (pin "1") (pinfunction "1_1") (pintype "passive"))
      (node (ref "U1") (pin "40") (pinfunction "PB4_40") (pintype "bidirectional"))
    )
    (net (code "44") (name "Net-(U1A-PB5)") (class "Default")
      (node (ref "J6") (pin "2") (pinfunction "2_2") (pintype "passive"))
      (node (ref "U1") (pin "41") (pinfunction "PB5_41") (pintype "bidirectional"))
    )
    (net (code "45") (name "Net-(U1A-PB6)") (class "Default")
      (node (ref "J6") (pin "3") (pinfunction "3_3") (pintype "passive"))
      (node (ref "U1") (pin "42") (pinfunction "PB6_42") (pintype "bidirectional"))
    )
    (net (code "46") (name "Net-(U1A-PB7)") (class "Default")
      (node (ref "J6") (pin "4") (pinfunction "4_4") (pintype "passive"))
      (node (ref "U1") (pin "43") (pinfunction "PB7_43") (pintype "bidirectional"))
    )
    (net (code "47") (name "Net-(U1A-PB8)") (class "Default")
      (node (ref "J6") (pin "5") (pinfunction "5_5") (pintype "passive"))
      (node (ref "U1") (pin "45") (pinfunction "PB8_45") (pintype "bidirectional"))
    )
    (net (code "48") (name "Net-(U1A-PB9)") (class "Default")
      (node (ref "J6") (pin "6") (pinfunction "6_6") (pintype "passive"))
      (node (ref "U1") (pin "46") (pinfunction "PB9_46") (pintype "bidirectional"))
    )
    (net (code "49") (name "Net-(U1A-PD0-OSC_IN)") (class "Default")
      (node (ref "C2") (pin "1") (pinfunction "1_1") (pintype "passive"))
      (node (ref "U1") (pin "5") (pinfunction "PD0-OSC_IN_5") (pintype "bidirectional"))
      (node (ref "X1") (pin "1") (pinfunction "1_1") (pintype "passive"))
    )
    (net (code "50") (name "Net-(U1A-PD1)") (class "Default")
      (node (ref "C4") (pin "1") (pinfunction "1_1") (pintype "passive"))
      (node (ref "U1") (pin "6") (pinfunction "PD1_6") (pintype "bidirectional"))
      (node (ref "X1") (pin "3") (pinfunction "3_3") (pintype "passive"))
    )
    (net (code "51") (name "Net-(U3-CPOUT)") (class "Default")
      (node (ref "C8") (pin "2") (pinfunction "2_2") (pintype "passive"))
      (node (ref "U3") (pin "20") (pinfunction "CPOUT_20") (pintype "passive"))
    )
    (net (code "52") (name "Net-(U3-REGOUT)") (class "Default")
      (node (ref "C6") (pin "2") (pinfunction "2_2") (pintype "passive"))
      (node (ref "U3") (pin "10") (pinfunction "REGOUT_10") (pintype "passive"))
    )
    (net (code "53") (name "Net-(U4-C+)") (class "Default")
      (node (ref "C5") (pin "2") (pinfunction "2_2") (pintype "passive"))
      (node (ref "U4") (pin "6") (pinfunction "C+_6") (pintype "passive"))
    )
    (net (code "54") (name "Net-(U4-C-)") (class "Default")
      (node (ref "C5") (pin "1") (pinfunction "1_1") (pintype "passive"))
      (node (ref "U4") (pin "4") (pinfunction "C-_4") (pintype "passive"))
    )
    (net (code "55") (name "V5") (class "Default")
      (node (ref "C10") (pin "2") (pinfunction "2_2") (pintype "passive"))
      (node (ref "C18") (pin "2") (pinfunction "2_2") (pintype "passive"))
      (node (ref "C19") (pin "1") (pinfunction "A_1") (pintype "passive"))
      (node (ref "C20") (pin "1") (pinfunction "A_1") (pintype "passive"))
      (node (ref "C9") (pin "2") (pinfunction "2_2") (pintype "passive"))
      (node (ref "J11") (pin "1") (pinfunction "1_1") (pintype "passive"))
      (node (ref "U4") (pin "1") (pinfunction "VOUT_1") (pintype "power_in"))
      (node (ref "U5") (pin "3") (pinfunction "Vin_3") (pintype "passive"))
      (node (ref "U6") (pin "3") (pinfunction "Vin_3") (pintype "passive"))
    )
    (net (code "56") (name "VBat") (class "Default")
      (node (ref "C13") (pin "2") (pinfunction "2_2") (pintype "passive"))
      (node (ref "C15") (pin "2") (pinfunction "2_2") (pintype "passive"))
      (node (ref "C16") (pin "2") (pinfunction "2_2") (pintype "passive"))
      (node (ref "C17") (pin "2") (pinfunction "2_2") (pintype "passive"))
      (node (ref "D1") (pin "2") (pinfunction "K_2") (pintype "passive"))
      (node (ref "D2") (pin "2") (pinfunction "K_2") (pintype "passive"))
      (node (ref "D3") (pin "2") (pinfunction "K_2") (pintype "passive"))
      (node (ref "D4") (pin "2") (pinfunction "K_2") (pintype "passive"))
      (node (ref "J2") (pin "2") (pinfunction "2_2") (pintype "passive"))
      (node (ref "J3") (pin "2") (pinfunction "2_2") (pintype "passive"))
      (node (ref "J4") (pin "2") (pinfunction "2_2") (pintype "passive"))
      (node (ref "J5") (pin "2") (pinfunction "2_2") (pintype "passive"))
      (node (ref "J7") (pin "2") (pinfunction "2_2") (pintype "passive"))
      (node (ref "L1") (pin "2") (pinfunction "2_2") (pintype "passive"))
      (node (ref "R24") (pin "2") (pinfunction "2_2") (pintype "passive"))
      (node (ref "R25") (pin "2") (pinfunction "2_2") (pintype "passive"))
      (node (ref "R26") (pin "2") (pinfunction "2_2") (pintype "passive"))
      (node (ref "R27") (pin "2") (pinfunction "2_2") (pintype "passive"))
      (node (ref "R4") (pin "1") (pinfunction "1_1") (pintype "passive"))
    )
    (net (code "57") (name "VCC") (class "Default")
      (node (ref "C21") (pin "1") (pinfunction "A_1") (pintype "passive"))
      (node (ref "C26") (pin "1") (pinfunction "1_1") (pintype "passive"))
      (node (ref "C7") (pin "2") (pinfunction "2_2") (pintype "passive"))
      (node (ref "J1") (pin "4") (pinfunction "4_4") (pintype "passive"))
      (node (ref "J8") (pin "4") (pinfunction "4_4") (pintype "passive"))
      (node (ref "R1") (pin "1") (pinfunction "1_1") (pintype "passive"))
      (node (ref "R14") (pin "1") (pinfunction "1_1") (pintype "passive"))
      (node (ref "R28") (pin "2") (pinfunction "2_2") (pintype "passive"))
      (node (ref "R3") (pin "1") (pinfunction "1_1") (pintype "passive"))
      (node (ref "R6") (pin "2") (pinfunction "2_2") (pintype "passive"))
      (node (ref "R7") (pin "2") (pinfunction "2_2") (pintype "passive"))
      (node (ref "R8") (pin "1") (pinfunction "1_1") (pintype "passive"))
      (node (ref "U1") (pin "24") (pinfunction "VDD_1_24") (pintype "power_in"))
      (node (ref "U1") (pin "36") (pinfunction "VDD_2_36") (pintype "power_in"))
      (node (ref "U1") (pin "48") (pinfunction "VDD_3_48") (pintype "power_in"))
      (node (ref "U1") (pin "9") (pinfunction "VDDA_9") (pintype "power_in"))
      (node (ref "U2") (pin "2") (pinfunction "VCC_2") (pintype "passive"))
      (node (ref "U3") (pin "8") (pinfunction "VLOGIC_8") (pintype "power_in"))
      (node (ref "U5") (pin "2") (pinfunction "Vout_2") (pintype "passive"))
    )
    (net (code "58") (name "Vsen") (class "Default")
      (node (ref "C22") (pin "1") (pinfunction "A_1") (pintype "passive"))
      (node (ref "C37") (pin "1") (pinfunction "1_1") (pintype "passive"))
      (node (ref "U3") (pin "13") (pinfunction "VDD_13") (pintype "power_in"))
      (node (ref "U6") (pin "2") (pinfunction "Vout_2") (pintype "passive"))
    )
    (net (code "59") (name "unconnected-(U1A-PA8-Pad29)") (class "Default")
      (node (ref "U1") (pin "29") (pinfunction "PA8_29") (pintype "bidirectional"))
    )
    (net (code "60") (name "unconnected-(U1A-PA11-Pad32)") (class "Default")
      (node (ref "U1") (pin "32") (pinfunction "PA11_32") (pintype "bidirectional"))
    )
    (net (code "61") (name "unconnected-(U1A-PA12-Pad33)") (class "Default")
      (node (ref "U1") (pin "33") (pinfunction "PA12_33") (pintype "bidirectional"))
    )
    (net (code "62") (name "unconnected-(U1A-PA15-Pad38)") (class "Default")
      (node (ref "U1") (pin "38") (pinfunction "PA15_38") (pintype "bidirectional"))
    )
    (net (code "63") (name "unconnected-(U1A-PB13-Pad26)") (class "Default")
      (node (ref "U1") (pin "26") (pinfunction "PB13_26") (pintype "bidirectional"))
    )
    (net (code "64") (name "unconnected-(U1A-PB14-Pad27)") (class "Default")
      (node (ref "U1") (pin "27") (pinfunction "PB14_27") (pintype "bidirectional"))
    )
    (net (code "65") (name "unconnected-(U1A-PB15-Pad28)") (class "Default")
      (node (ref "U1") (pin "28") (pinfunction "PB15_28") (pintype "bidirectional"))
    )
    (net (code "66") (name "unconnected-(U1A-PC14-OSC32_IN-Pad3)") (class "Default")
      (node (ref "U1") (pin "3") (pinfunction "PC14-OSC32_IN_3") (pintype "bidirectional"))
    )
    (net (code "67") (name "unconnected-(U1A-PC15-OSC32_OUT-Pad4)") (class "Default")
      (node (ref "U1") (pin "4") (pinfunction "PC15-OSC32_OUT_4") (pintype "bidirectional"))
    )
    (net (code "68") (name "unconnected-(U1B-VBAT-Pad1)") (class "Default")
      (node (ref "U1") (pin "1") (pinfunction "VBAT_1") (pintype "power_in"))
    )
    (net (code "69") (name "unconnected-(U3-AUX_CL-Pad7)") (class "Default")
      (node (ref "U3") (pin "7") (pinfunction "AUX_CL_7") (pintype "output"))
    )
    (net (code "70") (name "unconnected-(U3-AUX_DA-Pad6)") (class "Default")
      (node (ref "U3") (pin "6") (pinfunction "AUX_DA_6") (pintype "bidirectional"))
    )
    (net (code "71") (name "unconnected-(U3-CLKOUT-Pad22)") (class "Default")
      (node (ref "U3") (pin "22") (pinfunction "CLKOUT_22") (pintype "output"))
    )
    (net (code "72") (name "unconnected-(U3-EP-Pad25)") (class "Default")
      (node (ref "U3") (pin "25") (pinfunction "EP_25") (pintype "power_in"))
    )
    (net (code "73") (name "unconnected-(U3-NC-Pad2)") (class "Default")
      (node (ref "U3") (pin "2") (pinfunction "NC_2") (pintype "passive"))
    )
    (net (code "74") (name "unconnected-(U3-NC-Pad3)") (class "Default")
      (node (ref "U3") (pin "3") (pinfunction "NC_3") (pintype "passive"))
    )
    (net (code "75") (name "unconnected-(U3-NC-Pad4)") (class "Default")
      (node (ref "U3") (pin "4") (pinfunction "NC_4") (pintype "passive"))
    )
    (net (code "76") (name "unconnected-(U3-NC-Pad5)") (class "Default")
      (node (ref "U3") (pin "5") (pinfunction "NC_5") (pintype "passive"))
    )
    (net (code "77") (name "unconnected-(U3-NC-Pad14)") (class "Default")
      (node (ref "U3") (pin "14") (pinfunction "NC_14") (pintype "passive"))
    )
    (net (code "78") (name "unconnected-(U3-NC-Pad15)") (class "Default")
      (node (ref "U3") (pin "15") (pinfunction "NC_15") (pintype "passive"))
    )
    (net (code "79") (name "unconnected-(U3-NC-Pad16)") (class "Default")
      (node (ref "U3") (pin "16") (pinfunction "NC_16") (pintype "passive"))
    )
    (net (code "80") (name "unconnected-(U3-NC-Pad17)") (class "Default")
      (node (ref "U3") (pin "17") (pinfunction "NC_17") (pintype "passive"))
    )
    (net (code "81") (name "unconnected-(U3-RESV-Pad19)") (class "Default")
      (node (ref "U3") (pin "19") (pinfunction "RESV_19") (pintype "passive"))
    )
    (net (code "82") (name "unconnected-(U3-RESV-Pad21)") (class "Default")
      (node (ref "U3") (pin "21") (pinfunction "RESV_21") (pintype "passive"))
    )
  )
)
